# Condor2_Servo_REV_C.net
KiCad netlist of a schematic drawn in Altium Designer
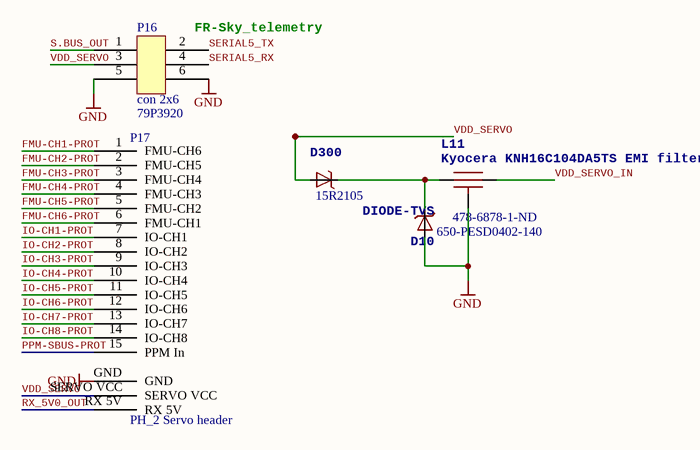
[diagram p0: Condor2_Servo_REV_C.SchDoc]

(export (version "E")
  (design (tool "Eeschema 10.0.6"))
  (components
    (comp (ref "D10")
      (value "DIODE-TVS")
      (footprint "0402-TVS")
      (description "Diode, TVS, 14VWM, 40VC, 0402, SMD")
      (fields (field (name "SUPPLIER PART NUMBER 1") "650-PESD0402-140"))
      (libsource (lib "CB_REV_C") (part "DIODE-TVS"))
    )
    (comp (ref "D300")
      (value "MSS1P4-M3")
      (footprint "MICROSMP")
      (description "Diode, Schottky, 40V, 1A, MicroSMP, SMD")
      (fields (field (name "SUPPLIER PART NUMBER 1") "15R2105"))
      (libsource (lib "CB_REV_C") (part "DIODE-SCHOTTKY_MSMP"))
    )
    (comp (ref "L11")
      (value "Kyocera KNH16C104DA5TS EMI filter")
      (footprint "KYOCERA-KNH16-DA")
      (description "Capacitor, Filter, 0.1uF, 25V, 2A, 0603, SMD")
      (fields (field (name "SUPPLIER PART NUMBER 1") "478-6878-1-ND"))
      (libsource (lib "CB_REV_C") (part "KNH16C104DA5TS"))
    )
    (comp (ref "P16")
      (value "con 2x6")
      (footprint "TSW-103-07-G-D")
      (description "Connector, Header, 6Pos, 2.54MM, Vert, THT, Au")
      (fields (field (name "SUPPLIER PART NUMBER 1") "79P3920"))
      (libsource (lib "CB_REV_C") (part "con 2x6"))
    )
    (comp (ref "P17")
      (value "PH_2 Servo header")
      (footprint "TSW-115-08-G-T-RA")
      (description "Connector, Header, 45Pos, 2.54MM, R/A, THT, Tin")
      (libsource (lib "CB_REV_C") (part "PH_2 Servo header"))
    )
  )
  (nets
    (net (code "1") (name "/FMU-CH1-PROT") (class "Default")
      (node (ref "P17") (pin "1") (pinfunction "FMU-CH6_1") (pintype "passive"))
    )
    (net (code "2") (name "/FMU-CH2-PROT") (class "Default")
      (node (ref "P17") (pin "2") (pinfunction "FMU-CH5_2") (pintype "passive"))
    )
    (net (code "3") (name "/FMU-CH3-PROT") (class "Default")
      (node (ref "P17") (pin "3") (pinfunction "FMU-CH4_3") (pintype "passive"))
    )
    (net (code "4") (name "/FMU-CH4-PROT") (class "Default")
      (node (ref "P17") (pin "4") (pinfunction "FMU-CH3_4") (pintype "passive"))
    )
    (net (code "5") (name "/FMU-CH5-PROT") (class "Default")
      (node (ref "P17") (pin "5") (pinfunction "FMU-CH2_5") (pintype "passive"))
    )
    (net (code "6") (name "/FMU-CH6-PROT") (class "Default")
      (node (ref "P17") (pin "6") (pinfunction "FMU-CH1_6") (pintype "passive"))
    )
    (net (code "7") (name "/IO-CH1-PROT") (class "Default")
      (node (ref "P17") (pin "7") (pinfunction "IO-CH1_7") (pintype "passive"))
    )
    (net (code "8") (name "/IO-CH2-PROT") (class "Default")
      (node (ref "P17") (pin "8") (pinfunction "IO-CH2_8") (pintype "passive"))
    )
    (net (code "9") (name "/IO-CH3-PROT") (class "Default")
      (node (ref "P17") (pin "9") (pinfunction "IO-CH3_9") (pintype "passive"))
    )
    (net (code "10") (name "/IO-CH4-PROT") (class "Default")
      (node (ref "P17") (pin "10") (pinfunction "IO-CH4_10") (pintype "passive"))
    )
    (net (code "11") (name "/IO-CH5-PROT") (class "Default")
      (node (ref "P17") (pin "11") (pinfunction "IO-CH5_11") (pintype "passive"))
    )
    (net (code "12") (name "/IO-CH6-PROT") (class "Default")
      (node (ref "P17") (pin "12") (pinfunction "IO-CH6_12") (pintype "passive"))
    )
    (net (code "13") (name "/IO-CH7-PROT") (class "Default")
      (node (ref "P17") (pin "13") (pinfunction "IO-CH7_13") (pintype "passive"))
    )
    (net (code "14") (name "/IO-CH8-PROT") (class "Default")
      (node (ref "P17") (pin "14") (pinfunction "IO-CH8_14") (pintype "passive"))
    )
    (net (code "15") (name "/PPM-SBUS-PROT") (class "Default")
      (node (ref "P17") (pin "15") (pinfunction "PPM_In_15") (pintype "passive"))
    )
    (net (code "16") (name "/RX_5V0_OUT") (class "Default")
      (node (ref "P17") (pin "RX_5V") (pinfunction "RX_5V_RX_5V") (pintype "passive"))
    )
    (net (code "17") (name "/S.BUS_OUT") (class "Default")
      (node (ref "P16") (pin "1") (pinfunction "1_1") (pintype "passive"))
    )
    (net (code "18") (name "/SERIAL5_RX") (class "Default")
      (node (ref "P16") (pin "4") (pinfunction "4_4") (pintype "passive"))
    )
    (net (code "19") (name "/SERIAL5_TX") (class "Default")
      (node (ref "P16") (pin "2") (pinfunction "2_2") (pintype "passive"))
    )
    (net (code "20") (name "/VDD_SERVO") (class "Default")
      (node (ref "D300") (pin "ANODE") (pinfunction "A_ANODE") (pintype "passive"))
      (node (ref "P16") (pin "3") (pinfunction "3_3") (pintype "passive"))
      (node (ref "P17") (pin "SERVO_VCC") (pinfunction "SERVO_VCC_SERVO_VCC") (pintype "passive"))
    )
    (net (code "21") (name "/VDD_SERVO_IN") (class "Default")
      (node (ref "L11") (pin "P$2") (pinfunction "P$2_P$2") (pintype "passive"))
    )
    (net (code "22") (name "GND") (class "Default")
      (node (ref "D10") (pin "A") (pinfunction "A_A") (pintype "passive"))
      (node (ref "L11") (pin "GND") (pinfunction "GND_GND") (pintype "passive"))
      (node (ref "P16") (pin "5") (pinfunction "5_5") (pintype "passive"))
      (node (ref "P16") (pin "6") (pinfunction "6_6") (pintype "passive"))
      (node (ref "P17") (pin "GND") (pinfunction "GND_GND") (pintype "passive"))
    )
    (net (code "23") (name "Net-(D300-C)") (class "Default")
      (node (ref "D10") (pin "C") (pinfunction "C_C") (pintype "passive"))
      (node (ref "D300") (pin "CATHODE") (pinfunction "C_CATHODE") (pintype "passive"))
      (node (ref "L11") (pin "P$1") (pinfunction "P$1_P$1") (pintype "passive"))
    )
  )
)
